# rony_hall_sensor.net
KiCad netlist of a schematic drawn in EAGLE
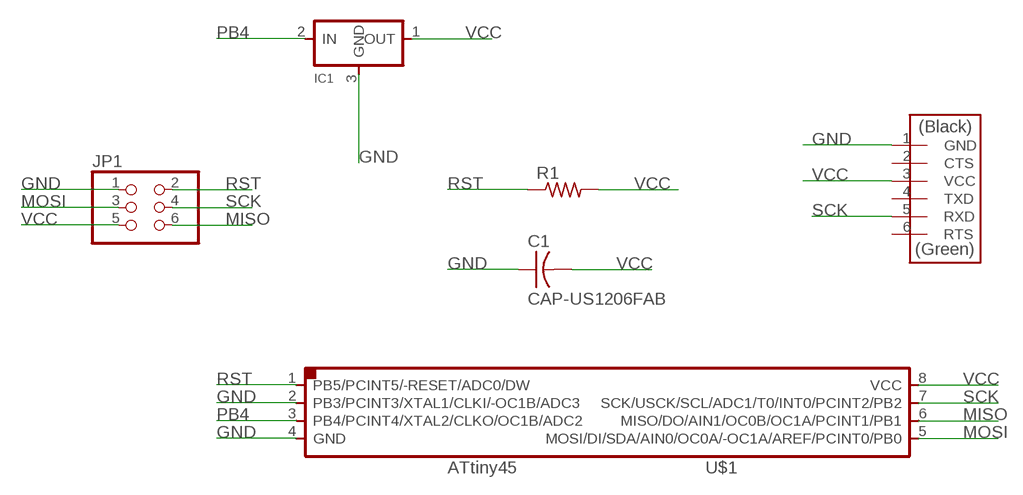
[diagram p0: schematic, sheet 1]

(export (version "E")
  (design (tool "Eeschema 10.0.6"))
  (components
    (comp (ref "C1")
      (value "CAP-US1206FAB")
      (footprint "eagle-import:C1206FAB")
      (libsource (lib "eagle-import") (part "CAP-US1206FAB"))
    )
    (comp (ref "IC1")
      (value "REGULATORSOT23")
      (footprint "eagle-import:SOT23")
      (libsource (lib "eagle-import") (part "REGULATORSOT23"))
    )
    (comp (ref "JP1")
      (value "PINHD-2X3-SMD")
      (footprint "eagle-import:2X03SMD")
      (libsource (lib "eagle-import") (part "PINHD-2X3-SMD"))
    )
    (comp (ref "R1")
      (value "RES-US1206FAB")
      (footprint "eagle-import:R1206FAB")
      (libsource (lib "eagle-import") (part "RES-US1206FAB"))
    )
    (comp (ref "U$1")
      (value "ATTINY45SI")
      (footprint "eagle-import:SOIC8")
      (libsource (lib "eagle-import") (part "ATTINY45SI"))
    )
    (comp (ref "U$2")
      (value "FTDI-SMD-HEADER")
      (footprint "eagle-import:1X06SMD")
      (libsource (lib "eagle-import") (part "FTDI-SMD-HEADER"))
    )
  )
  (nets
    (net (code "1") (name "/GND") (class "Default")
      (node (ref "C1") (pin "1") (pinfunction "1_1") (pintype "passive"))
      (node (ref "IC1") (pin "3") (pinfunction "GND_3") (pintype "bidirectional"))
      (node (ref "JP1") (pin "1") (pinfunction "1_1") (pintype "passive"))
      (node (ref "U$1") (pin "2") (pinfunction "PB3/PCINT3/XTAL1/CLKI/-OC1B/ADC3_2") (pintype "bidirectional"))
      (node (ref "U$1") (pin "4") (pinfunction "GND_4") (pintype "bidirectional"))
      (node (ref "U$2") (pin "1") (pinfunction "GND_1") (pintype "bidirectional"))
    )
    (net (code "2") (name "/MISO") (class "Default")
      (node (ref "JP1") (pin "6") (pinfunction "6_6") (pintype "passive"))
      (node (ref "U$1") (pin "6") (pinfunction "MISO/DO/AIN1/OC0B/OC1A/PCINT1/PB1_6") (pintype "bidirectional"))
    )
    (net (code "3") (name "/MOSI") (class "Default")
      (node (ref "JP1") (pin "3") (pinfunction "3_3") (pintype "passive"))
      (node (ref "U$1") (pin "5") (pinfunction "MOSI/DI/SDA/AIN0/OC0A/-OC1A/AREF/PCINT0/PB0_5") (pintype "bidirectional"))
    )
    (net (code "4") (name "/PB4") (class "Default")
      (node (ref "IC1") (pin "2") (pinfunction "IN_2") (pintype "bidirectional"))
      (node (ref "U$1") (pin "3") (pinfunction "PB4/PCINT4/XTAL2/CLKO/OC1B/ADC2_3") (pintype "bidirectional"))
    )
    (net (code "5") (name "/RST") (class "Default")
      (node (ref "JP1") (pin "2") (pinfunction "2_2") (pintype "passive"))
      (node (ref "R1") (pin "1") (pinfunction "1_1") (pintype "passive"))
      (node (ref "U$1") (pin "1") (pinfunction "PB5/PCINT5/-RESET/ADC0/DW_1") (pintype "bidirectional"))
    )
    (net (code "6") (name "/SCK") (class "Default")
      (node (ref "JP1") (pin "4") (pinfunction "4_4") (pintype "passive"))
      (node (ref "U$1") (pin "7") (pinfunction "SCK/USCK/SCL/ADC1/T0/INT0/PCINT2/PB2_7") (pintype "bidirectional"))
      (node (ref "U$2") (pin "5") (pinfunction "RXD_5") (pintype "bidirectional"))
    )
    (net (code "7") (name "/VCC") (class "Default")
      (node (ref "C1") (pin "2") (pinfunction "2_2") (pintype "passive"))
      (node (ref "IC1") (pin "1") (pinfunction "OUT_1") (pintype "bidirectional"))
      (node (ref "JP1") (pin "5") (pinfunction "5_5") (pintype "passive"))
      (node (ref "R1") (pin "2") (pinfunction "2_2") (pintype "passive"))
      (node (ref "U$1") (pin "8") (pinfunction "VCC_8") (pintype "bidirectional"))
      (node (ref "U$2") (pin "3") (pinfunction "VCC_3") (pintype "bidirectional"))
    )
    (net (code "8") (name "unconnected-(U$2-CTS-Pad2)") (class "Default")
      (node (ref "U$2") (pin "2") (pinfunction "CTS_2") (pintype "bidirectional"))
    )
    (net (code "9") (name "unconnected-(U$2-RTS-Pad6)") (class "Default")
      (node (ref "U$2") (pin "6") (pinfunction "RTS_6") (pintype "bidirectional"))
    )
    (net (code "10") (name "unconnected-(U$2-TXD-Pad4)") (class "Default")
      (node (ref "U$2") (pin "4") (pinfunction "TXD_4") (pintype "bidirectional"))
    )
  )
)
